# msp430_qfn16.net
KiCad netlist of a schematic drawn in EAGLE
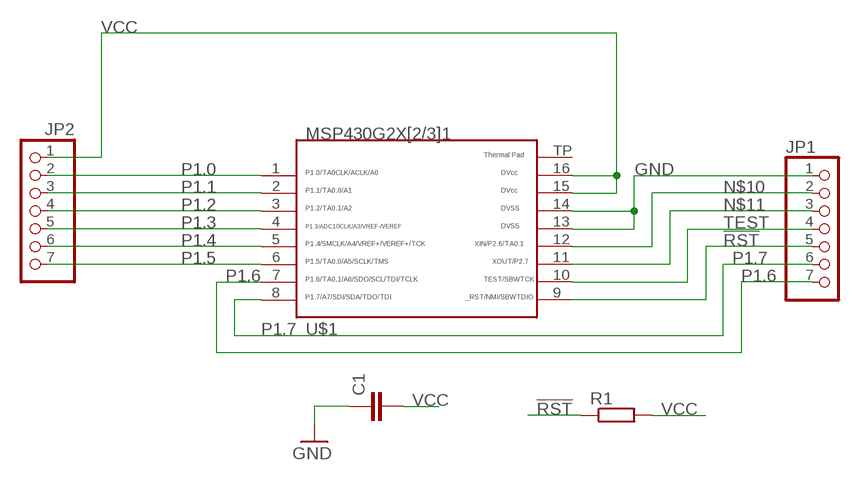
[diagram p0: schematic, sheet 1]

(export (version "E")
  (design (tool "Eeschema 10.0.6"))
  (components
    (comp (ref "C1")
      (value "C-EUC0805K")
      (footprint "eagle-import:C0805K")
      (libsource (lib "eagle-import") (part "C-EUC0805K"))
    )
    (comp (ref "JP1")
      (value "PINHD-1X7")
      (footprint "eagle-import:1X07")
      (libsource (lib "eagle-import") (part "PINHD-1X7"))
    )
    (comp (ref "JP2")
      (value "PINHD-1X7")
      (footprint "eagle-import:1X07")
      (libsource (lib "eagle-import") (part "PINHD-1X7"))
    )
    (comp (ref "R1")
      (value "R-EU_R0805")
      (footprint "eagle-import:R0805")
      (libsource (lib "eagle-import") (part "R-EU_R0805"))
    )
    (comp (ref "U$1")
      (value "G2X[2/3]1---RSA16")
      (footprint "eagle-import:RSA16")
      (libsource (lib "eagle-import") (part "G2X[2/3]1---RSA16"))
    )
  )
  (nets
    (net (code "1") (name "/N$10") (class "Default")
      (node (ref "JP1") (pin "2") (pinfunction "2_2") (pintype "passive"))
      (node (ref "U$1") (pin "12") (pinfunction "12_12") (pintype "bidirectional"))
    )
    (net (code "2") (name "/N$11") (class "Default")
      (node (ref "JP1") (pin "3") (pinfunction "3_3") (pintype "passive"))
      (node (ref "U$1") (pin "11") (pinfunction "11_11") (pintype "bidirectional"))
    )
    (net (code "3") (name "/P1.0") (class "Default")
      (node (ref "JP2") (pin "2") (pinfunction "2_2") (pintype "passive"))
      (node (ref "U$1") (pin "1") (pinfunction "1_1") (pintype "bidirectional"))
    )
    (net (code "4") (name "/P1.1") (class "Default")
      (node (ref "JP2") (pin "3") (pinfunction "3_3") (pintype "passive"))
      (node (ref "U$1") (pin "2") (pinfunction "2_2") (pintype "bidirectional"))
    )
    (net (code "5") (name "/P1.2") (class "Default")
      (node (ref "JP2") (pin "4") (pinfunction "4_4") (pintype "passive"))
      (node (ref "U$1") (pin "3") (pinfunction "3_3") (pintype "bidirectional"))
    )
    (net (code "6") (name "/P1.3") (class "Default")
      (node (ref "JP2") (pin "5") (pinfunction "5_5") (pintype "passive"))
      (node (ref "U$1") (pin "4") (pinfunction "4_4") (pintype "bidirectional"))
    )
    (net (code "7") (name "/P1.4") (class "Default")
      (node (ref "JP2") (pin "6") (pinfunction "6_6") (pintype "passive"))
      (node (ref "U$1") (pin "5") (pinfunction "5_5") (pintype "bidirectional"))
    )
    (net (code "8") (name "/P1.5") (class "Default")
      (node (ref "JP2") (pin "7") (pinfunction "7_7") (pintype "passive"))
      (node (ref "U$1") (pin "6") (pinfunction "6_6") (pintype "bidirectional"))
    )
    (net (code "9") (name "/P1.6") (class "Default")
      (node (ref "JP1") (pin "7") (pinfunction "7_7") (pintype "passive"))
      (node (ref "U$1") (pin "7") (pinfunction "7_7") (pintype "bidirectional"))
    )
    (net (code "10") (name "/P1.7") (class "Default")
      (node (ref "JP1") (pin "6") (pinfunction "6_6") (pintype "passive"))
      (node (ref "U$1") (pin "8") (pinfunction "8_8") (pintype "bidirectional"))
    )
    (net (code "11") (name "/TEST") (class "Default")
      (node (ref "JP1") (pin "4") (pinfunction "4_4") (pintype "passive"))
      (node (ref "U$1") (pin "10") (pinfunction "10_10") (pintype "bidirectional"))
    )
    (net (code "12") (name "/VCC") (class "Default")
      (node (ref "C1") (pin "2") (pinfunction "2_2") (pintype "passive"))
      (node (ref "JP2") (pin "1") (pinfunction "1_1") (pintype "passive"))
      (node (ref "R1") (pin "2") (pinfunction "2_2") (pintype "passive"))
      (node (ref "U$1") (pin "15") (pinfunction "15_15") (pintype "bidirectional"))
      (node (ref "U$1") (pin "16") (pinfunction "16_16") (pintype "bidirectional"))
    )
    (net (code "13") (name "/~{RST}") (class "Default")
      (node (ref "JP1") (pin "5") (pinfunction "5_5") (pintype "passive"))
      (node (ref "R1") (pin "1") (pinfunction "1_1") (pintype "passive"))
      (node (ref "U$1") (pin "9") (pinfunction "9_9") (pintype "bidirectional"))
    )
    (net (code "14") (name "GND") (class "Default")
      (node (ref "C1") (pin "1") (pinfunction "1_1") (pintype "passive"))
      (node (ref "JP1") (pin "1") (pinfunction "1_1") (pintype "passive"))
      (node (ref "U$1") (pin "13") (pinfunction "13_13") (pintype "bidirectional"))
      (node (ref "U$1") (pin "14") (pinfunction "14_14") (pintype "bidirectional"))
    )
    (net (code "15") (name "unconnected-(U$1-PadTP)") (class "Default")
      (node (ref "U$1") (pin "TP") (pinfunction "TP_TP") (pintype "bidirectional"))
    )
  )
)
